# Sheet1.net
KiCad netlist of a schematic drawn in Altium Designer
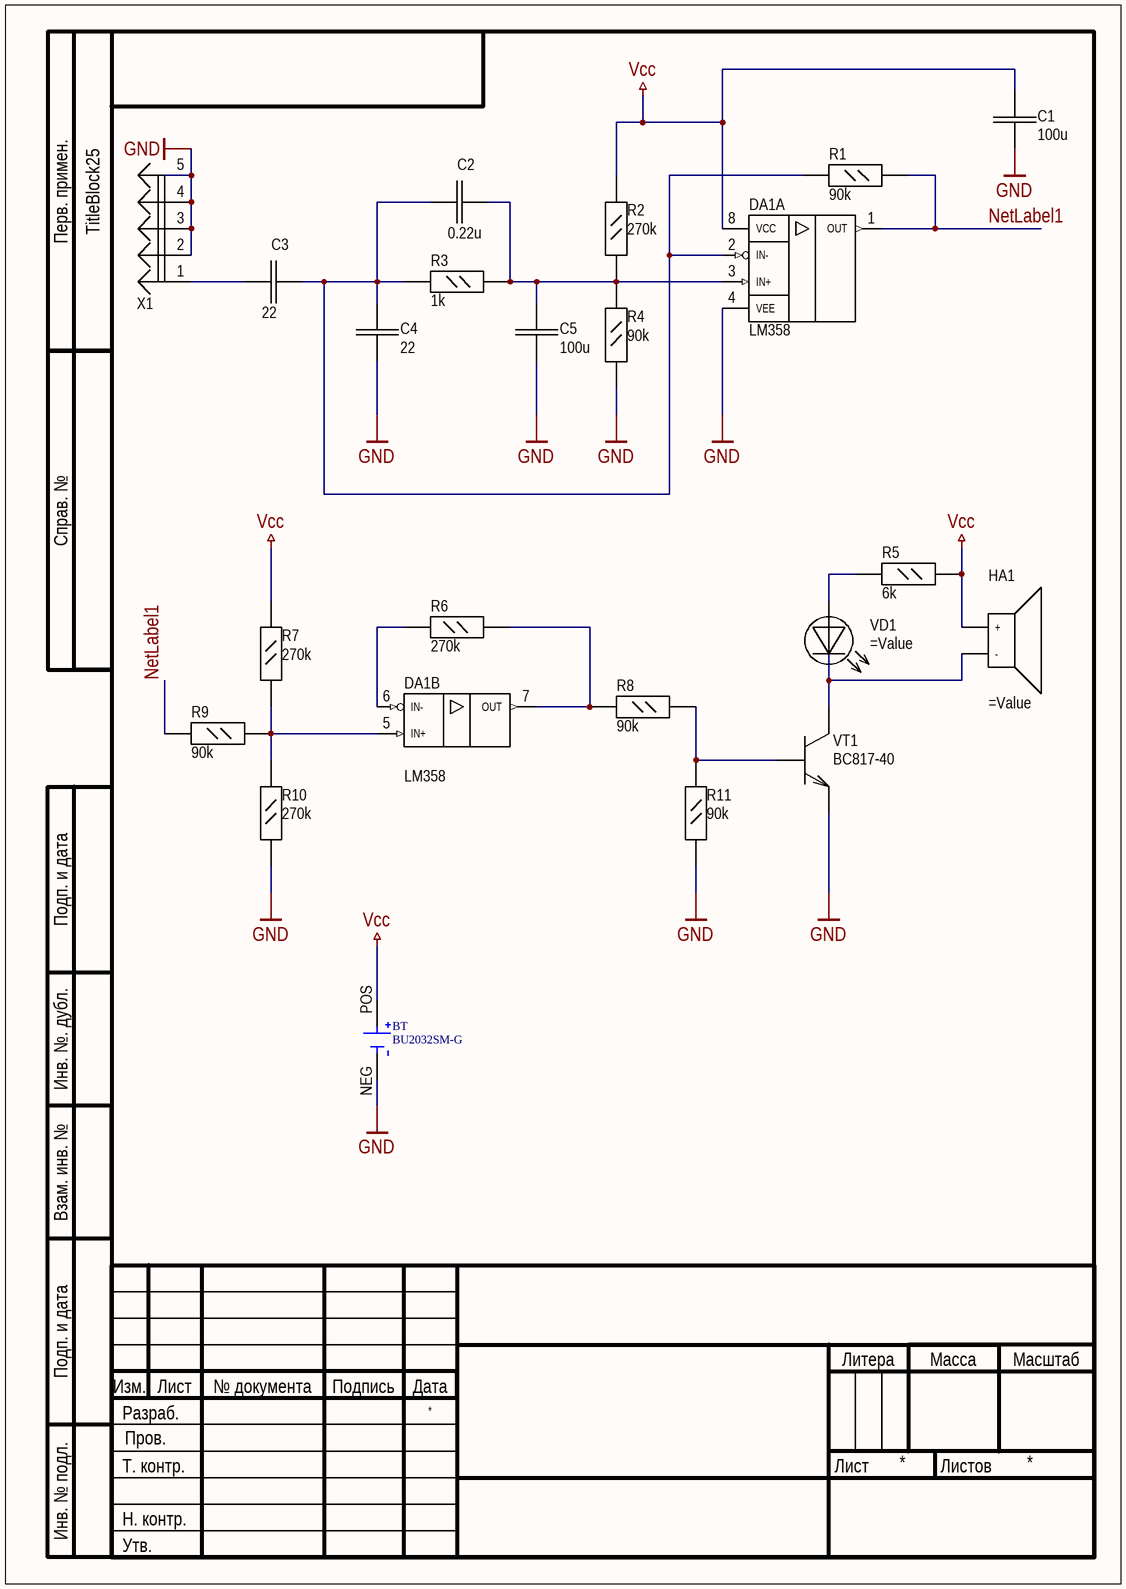
[diagram p0: Sheet1.SchDoc]

(export (version "E")
  (design (tool "Eeschema 10.0.6"))
  (components
    (comp (ref "BT")
      (value "BU2032SM-G")
      (footprint "SnapEDApcb:BAT_BU2032SM-G")
      (description "BATTERY HOLDER COIN 20MM SMD")
      (fields (field (name "MF") "MPD"))
      (libsource (lib "SnapEDAsch") (part "BU2032SM-G"))
    )
    (comp (ref "C1")
      (value "100u")
      (footprint "RESC0603")
      (description "Конденсатор СМД")
      (libsource (lib "library") (part "Cap-SMD-0603"))
    )
    (comp (ref "C2")
      (value "0.22u")
      (footprint "RESC0603")
      (description "Конденсатор СМД")
      (libsource (lib "library") (part "Cap-SMD-0603"))
    )
    (comp (ref "C3")
      (value "22")
      (footprint "RESC0603")
      (description "Конденсатор СМД")
      (libsource (lib "library") (part "Cap-SMD-0603"))
    )
    (comp (ref "C4")
      (value "22")
      (footprint "RESC0603")
      (description "Конденсатор СМД")
      (libsource (lib "library") (part "Cap-SMD-0603"))
    )
    (comp (ref "C5")
      (value "100u")
      (footprint "RESC0603")
      (description "Конденсатор СМД")
      (libsource (lib "library") (part "Cap-SMD-0603"))
    )
    (comp (ref "DA1")
      (value "LM358")
      (footprint "SOIC-8")
      (description "Микросхема, операционный усилитель")
      (libsource (lib "library") (part "LM1458"))
    )
    (comp (ref "HA1")
      (value "~")
      (footprint "PKLCS1212E4001")
      (description "Пьезоизлучатель")
      (libsource (lib "library") (part "SMA-24L-P10"))
    )
    (comp (ref "R1")
      (value "90k")
      (footprint "RESC0603")
      (description "Резистор СМД")
      (libsource (lib "") (part "Res-0603-0.25W_1"))
    )
    (comp (ref "R2")
      (value "270k")
      (footprint "RESC0603")
      (description "Резистор СМД")
      (libsource (lib "library") (part "Res-0603-0.25W"))
    )
    (comp (ref "R3")
      (value "1k")
      (footprint "RESC0603")
      (description "Резистор СМД")
      (libsource (lib "") (part "Res-0603-0.25W_1"))
    )
    (comp (ref "R4")
      (value "90k")
      (footprint "RESC0603")
      (description "Резистор СМД")
      (libsource (lib "library") (part "Res-0603-0.25W"))
    )
    (comp (ref "R5")
      (value "6k")
      (footprint "RESC0603")
      (description "Резистор СМД")
      (libsource (lib "") (part "Res-0603-0.25W_1"))
    )
    (comp (ref "R6")
      (value "270k")
      (footprint "RESC0603")
      (description "Резистор СМД")
      (libsource (lib "") (part "Res-0603-0.25W_2"))
    )
    (comp (ref "R7")
      (value "270k")
      (footprint "RESC0603")
      (description "Резистор СМД")
      (libsource (lib "library") (part "Res-0603-0.25W"))
    )
    (comp (ref "R8")
      (value "90k")
      (footprint "RESC0603")
      (description "Резистор СМД")
      (libsource (lib "") (part "Res-0603-0.25W_1"))
    )
    (comp (ref "R9")
      (value "90k")
      (footprint "RESC0603")
      (description "Резистор СМД")
      (libsource (lib "") (part "Res-0603-0.25W_1"))
    )
    (comp (ref "R10")
      (value "270k")
      (footprint "RESC0603")
      (description "Резистор СМД")
      (libsource (lib "library") (part "Res-0603-0.25W"))
    )
    (comp (ref "R11")
      (value "90k")
      (footprint "RESC0603")
      (description "Резистор СМД")
      (libsource (lib "library") (part "Res-0603-0.25W"))
    )
    (comp (ref "VD1")
      (value "~")
      (footprint "RESC0603")
      (description "Светодиод")
      (libsource (lib "library") (part "Led"))
    )
    (comp (ref "VT1")
      (value "BC817-40")
      (footprint "SOT-23")
      (description "Транзистор биполярный  NPN")
      (libsource (lib "library") (part "Transistor NPN"))
    )
    (comp (ref "X1")
      (value "~")
      (footprint "CONSMA008G")
      (description "Разъем 5, папа")
      (libsource (lib "library") (part "Header 5M"))
    )
  )
  (nets
    (net (code "1") (name "/NetLabel1") (class "Default")
      (node (ref "DA1") (pin "1") (pinfunction "OUT_1") (pintype "output"))
      (node (ref "R1") (pin "2") (pinfunction "2_2") (pintype "passive"))
      (node (ref "R9") (pin "1") (pinfunction "1_1") (pintype "passive"))
    )
    (net (code "2") (name "GND") (class "Default")
      (node (ref "BT") (pin "NEG") (pinfunction "NEG_NEG") (pintype "passive"))
      (node (ref "C1") (pin "1") (pinfunction "1_1") (pintype "passive"))
      (node (ref "C4") (pin "1") (pinfunction "1_1") (pintype "passive"))
      (node (ref "C5") (pin "1") (pinfunction "1_1") (pintype "passive"))
      (node (ref "DA1") (pin "4") (pinfunction "VEE_4") (pintype "passive"))
      (node (ref "R10") (pin "1") (pinfunction "1_1") (pintype "passive"))
      (node (ref "R11") (pin "1") (pinfunction "1_1") (pintype "passive"))
      (node (ref "R4") (pin "1") (pinfunction "1_1") (pintype "passive"))
      (node (ref "VT1") (pin "1") (pinfunction "E_1") (pintype "passive"))
      (node (ref "X1") (pin "2") (pinfunction "2_2") (pintype "passive"))
      (node (ref "X1") (pin "3") (pinfunction "3_3") (pintype "passive"))
      (node (ref "X1") (pin "4") (pinfunction "4_4") (pintype "passive"))
      (node (ref "X1") (pin "5") (pinfunction "5_5") (pintype "passive"))
    )
    (net (code "3") (name "Net-(C3-Pad1)") (class "Default")
      (node (ref "C3") (pin "1") (pinfunction "1_1") (pintype "passive"))
      (node (ref "X1") (pin "1") (pinfunction "1_1") (pintype "passive"))
    )
    (net (code "4") (name "Net-(DA1A-IN+)") (class "Default")
      (node (ref "C2") (pin "2") (pinfunction "2_2") (pintype "passive"))
      (node (ref "C5") (pin "2") (pinfunction "2_2") (pintype "passive"))
      (node (ref "DA1") (pin "3") (pinfunction "IN+_3") (pintype "input"))
      (node (ref "R2") (pin "1") (pinfunction "1_1") (pintype "passive"))
      (node (ref "R3") (pin "2") (pinfunction "2_2") (pintype "passive"))
      (node (ref "R4") (pin "2") (pinfunction "2_2") (pintype "passive"))
    )
    (net (code "5") (name "Net-(DA1A-IN-)") (class "Default")
      (node (ref "C2") (pin "1") (pinfunction "1_1") (pintype "passive"))
      (node (ref "C3") (pin "2") (pinfunction "2_2") (pintype "passive"))
      (node (ref "C4") (pin "2") (pinfunction "2_2") (pintype "passive"))
      (node (ref "DA1") (pin "2") (pinfunction "IN-_2") (pintype "input"))
      (node (ref "R1") (pin "1") (pinfunction "1_1") (pintype "passive"))
      (node (ref "R3") (pin "1") (pinfunction "1_1") (pintype "passive"))
    )
    (net (code "6") (name "Net-(DA1B-IN+)") (class "Default")
      (node (ref "DA1") (pin "5") (pinfunction "IN+_5") (pintype "input"))
      (node (ref "R10") (pin "2") (pinfunction "2_2") (pintype "passive"))
      (node (ref "R7") (pin "1") (pinfunction "1_1") (pintype "passive"))
      (node (ref "R9") (pin "2") (pinfunction "2_2") (pintype "passive"))
    )
    (net (code "7") (name "Net-(DA1B-IN-)") (class "Default")
      (node (ref "DA1") (pin "6") (pinfunction "IN-_6") (pintype "input"))
      (node (ref "R6") (pin "2") (pinfunction "2_2") (pintype "passive"))
    )
    (net (code "8") (name "Net-(DA1B-OUT)") (class "Default")
      (node (ref "DA1") (pin "7") (pinfunction "OUT_7") (pintype "output"))
      (node (ref "R6") (pin "1") (pinfunction "1_1") (pintype "passive"))
      (node (ref "R8") (pin "1") (pinfunction "1_1") (pintype "passive"))
    )
    (net (code "9") (name "Net-(HA1--)") (class "Default")
      (node (ref "HA1") (pin "2") (pinfunction "-_2") (pintype "passive"))
      (node (ref "VD1") (pin "1") (pinfunction "K_1") (pintype "passive"))
      (node (ref "VT1") (pin "3") (pinfunction "C_3") (pintype "passive"))
    )
    (net (code "10") (name "Net-(VD1-A)") (class "Default")
      (node (ref "R5") (pin "1") (pinfunction "1_1") (pintype "passive"))
      (node (ref "VD1") (pin "2") (pinfunction "A_2") (pintype "passive"))
    )
    (net (code "11") (name "Net-(VT1-B)") (class "Default")
      (node (ref "R11") (pin "2") (pinfunction "2_2") (pintype "passive"))
      (node (ref "R8") (pin "2") (pinfunction "2_2") (pintype "passive"))
      (node (ref "VT1") (pin "2") (pinfunction "B_2") (pintype "passive"))
    )
    (net (code "12") (name "Vcc") (class "Default")
      (node (ref "BT") (pin "POS") (pinfunction "POS_POS") (pintype "passive"))
      (node (ref "C1") (pin "2") (pinfunction "2_2") (pintype "passive"))
      (node (ref "DA1") (pin "8") (pinfunction "VCC_8") (pintype "passive"))
      (node (ref "HA1") (pin "1") (pinfunction "+_1") (pintype "passive"))
      (node (ref "R2") (pin "2") (pinfunction "2_2") (pintype "passive"))
      (node (ref "R5") (pin "2") (pinfunction "2_2") (pintype "passive"))
      (node (ref "R7") (pin "2") (pinfunction "2_2") (pintype "passive"))
    )
  )
)
